# fpga.net
KiCad netlist of a schematic drawn in Altium Designer
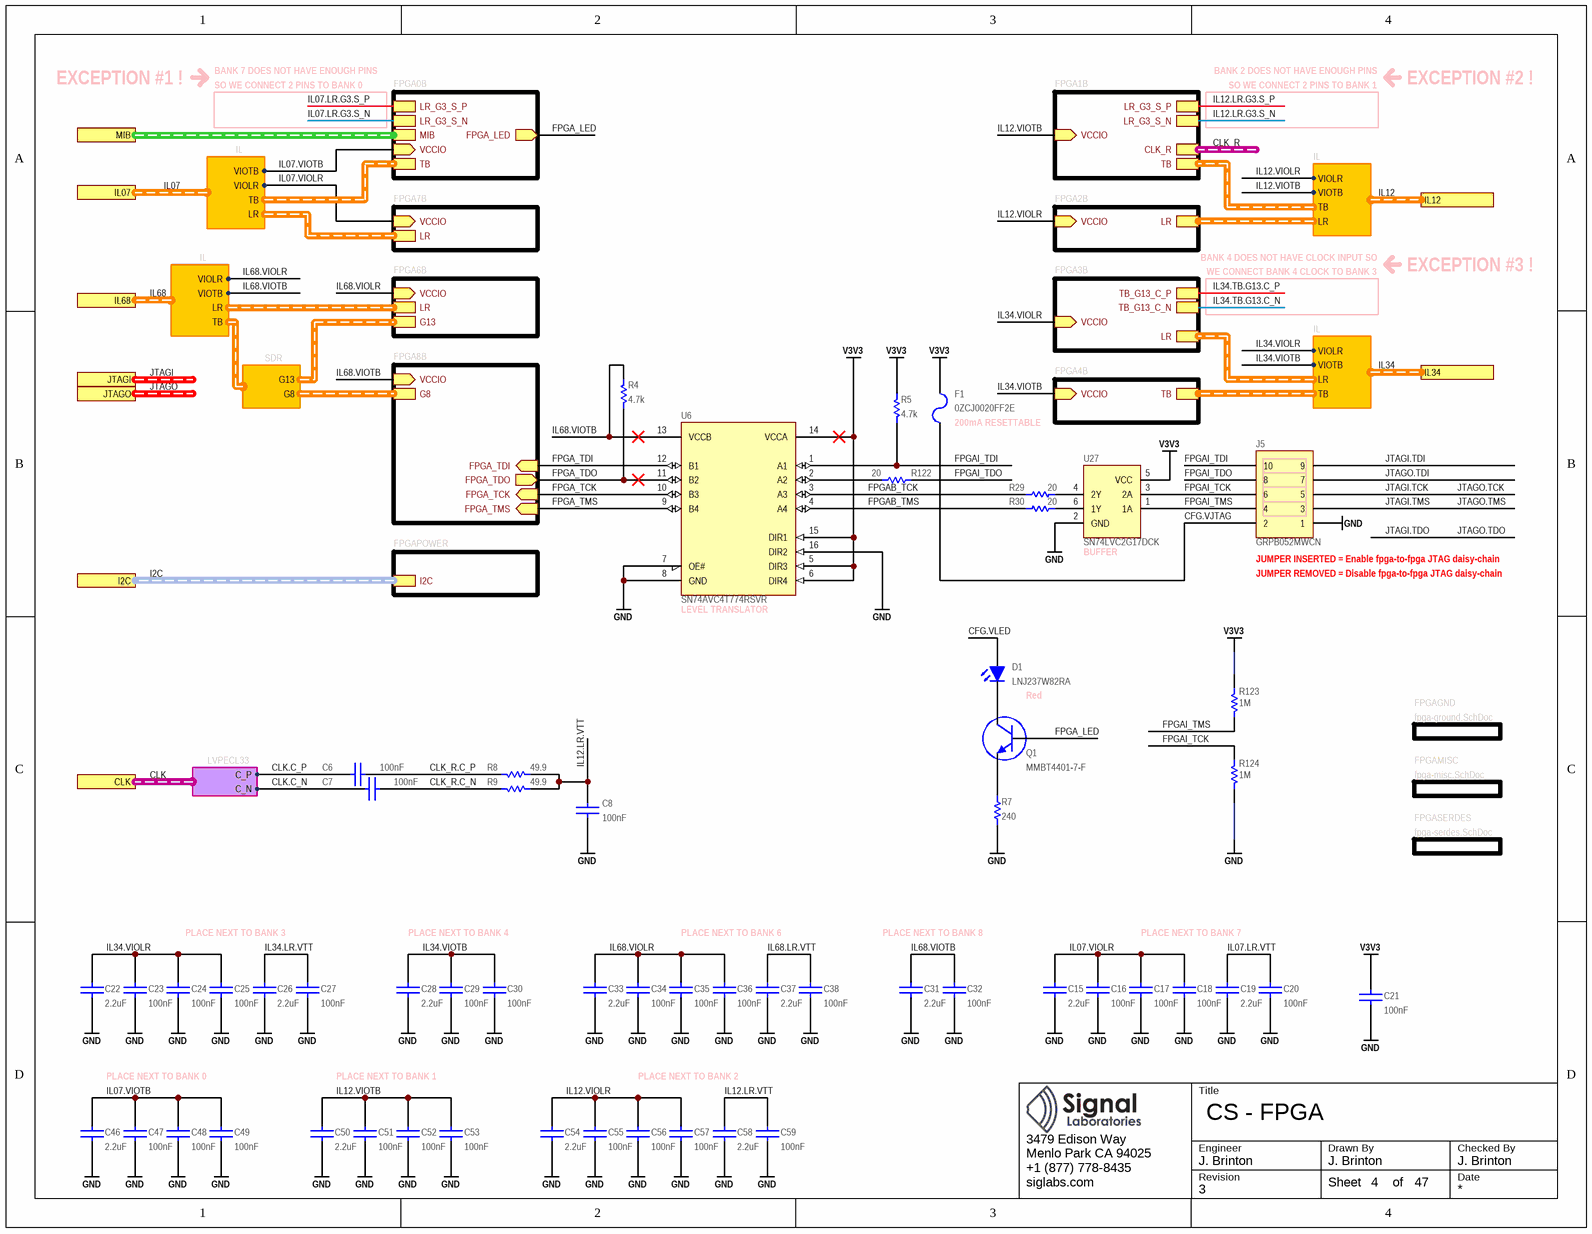
[diagram p0: fpga.SchDoc]

(export (version "E")
  (design (tool "Eeschema 10.0.6"))
  (components
    (comp (ref "C6")
      (value "100nF")
      (footprint "CAPC100X50X55L25N")
      (description "Ceramic Capacitor 100nF ±10% 50V X7R 0402")
      (fields (field (name "MANUFACTURER") "Murata") (field (name "TOLERANCE") "±10%"))
      (libsource (lib "generic") (part "CAP"))
    )
    (comp (ref "C7")
      (value "100nF")
      (footprint "CAPC100X50X55L25N")
      (description "Ceramic Capacitor 100nF ±10% 50V X7R 0402")
      (fields (field (name "MANUFACTURER") "Murata") (field (name "TOLERANCE") "±10%"))
      (libsource (lib "generic") (part "CAP"))
    )
    (comp (ref "C8")
      (value "100nF")
      (footprint "CAPC100X50X55L25N")
      (description "Ceramic Capacitor 100nF ±10% 50V X7R 0402")
      (fields (field (name "MANUFACTURER") "Murata") (field (name "TOLERANCE") "±10%"))
      (libsource (lib "generic") (part "CAP"))
    )
    (comp (ref "C15")
      (value "2.2uF")
      (footprint "CAPC160X80X90L20N")
      (description "Ceramic Capacitor 2.2uF ±20% 10V X7R 0603")
      (fields (field (name "MANUFACTURER") "TDK") (field (name "TOLERANCE") "±20%"))
      (libsource (lib "generic") (part "CAP"))
    )
    (comp (ref "C16")
      (value "100nF")
      (footprint "CAPC100X50X55L25N")
      (description "Ceramic Capacitor 100nF ±10% 50V X7R 0402")
      (fields (field (name "MANUFACTURER") "Murata") (field (name "TOLERANCE") "±10%"))
      (libsource (lib "generic") (part "CAP"))
    )
    (comp (ref "C17")
      (value "100nF")
      (footprint "CAPC100X50X55L25N")
      (description "Ceramic Capacitor 100nF ±10% 50V X7R 0402")
      (fields (field (name "MANUFACTURER") "Murata") (field (name "TOLERANCE") "±10%"))
      (libsource (lib "generic") (part "CAP"))
    )
    (comp (ref "C18")
      (value "100nF")
      (footprint "CAPC100X50X55L25N")
      (description "Ceramic Capacitor 100nF ±10% 50V X7R 0402")
      (fields (field (name "MANUFACTURER") "Murata") (field (name "TOLERANCE") "±10%"))
      (libsource (lib "generic") (part "CAP"))
    )
    (comp (ref "C19")
      (value "2.2uF")
      (footprint "CAPC160X80X90L20N")
      (description "Ceramic Capacitor 2.2uF ±20% 10V X7R 0603")
      (fields (field (name "MANUFACTURER") "TDK") (field (name "TOLERANCE") "±20%"))
      (libsource (lib "generic") (part "CAP"))
    )
    (comp (ref "C20")
      (value "100nF")
      (footprint "CAPC100X50X55L25N")
      (description "Ceramic Capacitor 100nF ±10% 50V X7R 0402")
      (fields (field (name "MANUFACTURER") "Murata") (field (name "TOLERANCE") "±10%"))
      (libsource (lib "generic") (part "CAP"))
    )
    (comp (ref "C21")
      (value "100nF")
      (footprint "CAPC100X50X55L25N")
      (description "Ceramic Capacitor 100nF ±10% 50V X7R 0402")
      (fields (field (name "MANUFACTURER") "Murata") (field (name "TOLERANCE") "±10%"))
      (libsource (lib "generic") (part "CAP"))
    )
    (comp (ref "C22")
      (value "2.2uF")
      (footprint "CAPC160X80X90L20N")
      (description "Ceramic Capacitor 2.2uF ±20% 10V X7R 0603")
      (fields (field (name "MANUFACTURER") "TDK") (field (name "TOLERANCE") "±20%"))
      (libsource (lib "generic") (part "CAP"))
    )
    (comp (ref "C23")
      (value "100nF")
      (footprint "CAPC100X50X55L25N")
      (description "Ceramic Capacitor 100nF ±10% 50V X7R 0402")
      (fields (field (name "MANUFACTURER") "Murata") (field (name "TOLERANCE") "±10%"))
      (libsource (lib "generic") (part "CAP"))
    )
    (comp (ref "C24")
      (value "100nF")
      (footprint "CAPC100X50X55L25N")
      (description "Ceramic Capacitor 100nF ±10% 50V X7R 0402")
      (fields (field (name "MANUFACTURER") "Murata") (field (name "TOLERANCE") "±10%"))
      (libsource (lib "generic") (part "CAP"))
    )
    (comp (ref "C25")
      (value "100nF")
      (footprint "CAPC100X50X55L25N")
      (description "Ceramic Capacitor 100nF ±10% 50V X7R 0402")
      (fields (field (name "MANUFACTURER") "Murata") (field (name "TOLERANCE") "±10%"))
      (libsource (lib "generic") (part "CAP"))
    )
    (comp (ref "C26")
      (value "2.2uF")
      (footprint "CAPC160X80X90L20N")
      (description "Ceramic Capacitor 2.2uF ±20% 10V X7R 0603")
      (fields (field (name "MANUFACTURER") "TDK") (field (name "TOLERANCE") "±20%"))
      (libsource (lib "generic") (part "CAP"))
    )
    (comp (ref "C27")
      (value "100nF")
      (footprint "CAPC100X50X55L25N")
      (description "Ceramic Capacitor 100nF ±10% 50V X7R 0402")
      (fields (field (name "MANUFACTURER") "Murata") (field (name "TOLERANCE") "±10%"))
      (libsource (lib "generic") (part "CAP"))
    )
    (comp (ref "C28")
      (value "2.2uF")
      (footprint "CAPC160X80X90L20N")
      (description "Ceramic Capacitor 2.2uF ±20% 10V X7R 0603")
      (fields (field (name "MANUFACTURER") "TDK") (field (name "TOLERANCE") "±20%"))
      (libsource (lib "generic") (part "CAP"))
    )
    (comp (ref "C29")
      (value "100nF")
      (footprint "CAPC100X50X55L25N")
      (description "Ceramic Capacitor 100nF ±10% 50V X7R 0402")
      (fields (field (name "MANUFACTURER") "Murata") (field (name "TOLERANCE") "±10%"))
      (libsource (lib "generic") (part "CAP"))
    )
    (comp (ref "C30")
      (value "100nF")
      (footprint "CAPC100X50X55L25N")
      (description "Ceramic Capacitor 100nF ±10% 50V X7R 0402")
      (fields (field (name "MANUFACTURER") "Murata") (field (name "TOLERANCE") "±10%"))
      (libsource (lib "generic") (part "CAP"))
    )
    (comp (ref "C31")
      (value "2.2uF")
      (footprint "CAPC160X80X90L20N")
      (description "Ceramic Capacitor 2.2uF ±20% 10V X7R 0603")
      (fields (field (name "MANUFACTURER") "TDK") (field (name "TOLERANCE") "±20%"))
      (libsource (lib "generic") (part "CAP"))
    )
    (comp (ref "C32")
      (value "100nF")
      (footprint "CAPC100X50X55L25N")
      (description "Ceramic Capacitor 100nF ±10% 50V X7R 0402")
      (fields (field (name "MANUFACTURER") "Murata") (field (name "TOLERANCE") "±10%"))
      (libsource (lib "generic") (part "CAP"))
    )
    (comp (ref "C33")
      (value "2.2uF")
      (footprint "CAPC160X80X90L20N")
      (description "Ceramic Capacitor 2.2uF ±20% 10V X7R 0603")
      (fields (field (name "MANUFACTURER") "TDK") (field (name "TOLERANCE") "±20%"))
      (libsource (lib "generic") (part "CAP"))
    )
    (comp (ref "C34")
      (value "100nF")
      (footprint "CAPC100X50X55L25N")
      (description "Ceramic Capacitor 100nF ±10% 50V X7R 0402")
      (fields (field (name "MANUFACTURER") "Murata") (field (name "TOLERANCE") "±10%"))
      (libsource (lib "generic") (part "CAP"))
    )
    (comp (ref "C35")
      (value "100nF")
      (footprint "CAPC100X50X55L25N")
      (description "Ceramic Capacitor 100nF ±10% 50V X7R 0402")
      (fields (field (name "MANUFACTURER") "Murata") (field (name "TOLERANCE") "±10%"))
      (libsource (lib "generic") (part "CAP"))
    )
    (comp (ref "C36")
      (value "100nF")
      (footprint "CAPC100X50X55L25N")
      (description "Ceramic Capacitor 100nF ±10% 50V X7R 0402")
      (fields (field (name "MANUFACTURER") "Murata") (field (name "TOLERANCE") "±10%"))
      (libsource (lib "generic") (part "CAP"))
    )
    (comp (ref "C37")
      (value "2.2uF")
      (footprint "CAPC160X80X90L20N")
      (description "Ceramic Capacitor 2.2uF ±20% 10V X7R 0603")
      (fields (field (name "MANUFACTURER") "TDK") (field (name "TOLERANCE") "±20%"))
      (libsource (lib "generic") (part "CAP"))
    )
    (comp (ref "C38")
      (value "100nF")
      (footprint "CAPC100X50X55L25N")
      (description "Ceramic Capacitor 100nF ±10% 50V X7R 0402")
      (fields (field (name "MANUFACTURER") "Murata") (field (name "TOLERANCE") "±10%"))
      (libsource (lib "generic") (part "CAP"))
    )
    (comp (ref "C46")
      (value "2.2uF")
      (footprint "CAPC160X80X90L20N")
      (description "Ceramic Capacitor 2.2uF ±20% 10V X7R 0603")
      (fields (field (name "MANUFACTURER") "TDK") (field (name "TOLERANCE") "±20%"))
      (libsource (lib "generic") (part "CAP"))
    )
    (comp (ref "C47")
      (value "100nF")
      (footprint "CAPC100X50X55L25N")
      (description "Ceramic Capacitor 100nF ±10% 50V X7R 0402")
      (fields (field (name "MANUFACTURER") "Murata") (field (name "TOLERANCE") "±10%"))
      (libsource (lib "generic") (part "CAP"))
    )
    (comp (ref "C48")
      (value "100nF")
      (footprint "CAPC100X50X55L25N")
      (description "Ceramic Capacitor 100nF ±10% 50V X7R 0402")
      (fields (field (name "MANUFACTURER") "Murata") (field (name "TOLERANCE") "±10%"))
      (libsource (lib "generic") (part "CAP"))
    )
    (comp (ref "C49")
      (value "100nF")
      (footprint "CAPC100X50X55L25N")
      (description "Ceramic Capacitor 100nF ±10% 50V X7R 0402")
      (fields (field (name "MANUFACTURER") "Murata") (field (name "TOLERANCE") "±10%"))
      (libsource (lib "generic") (part "CAP"))
    )
    (comp (ref "C50")
      (value "2.2uF")
      (footprint "CAPC160X80X90L20N")
      (description "Ceramic Capacitor 2.2uF ±20% 10V X7R 0603")
      (fields (field (name "MANUFACTURER") "TDK") (field (name "TOLERANCE") "±20%"))
      (libsource (lib "generic") (part "CAP"))
    )
    (comp (ref "C51")
      (value "100nF")
      (footprint "CAPC100X50X55L25N")
      (description "Ceramic Capacitor 100nF ±10% 50V X7R 0402")
      (fields (field (name "MANUFACTURER") "Murata") (field (name "TOLERANCE") "±10%"))
      (libsource (lib "generic") (part "CAP"))
    )
    (comp (ref "C52")
      (value "100nF")
      (footprint "CAPC100X50X55L25N")
      (description "Ceramic Capacitor 100nF ±10% 50V X7R 0402")
      (fields (field (name "MANUFACTURER") "Murata") (field (name "TOLERANCE") "±10%"))
      (libsource (lib "generic") (part "CAP"))
    )
    (comp (ref "C53")
      (value "100nF")
      (footprint "CAPC100X50X55L25N")
      (description "Ceramic Capacitor 100nF ±10% 50V X7R 0402")
      (fields (field (name "MANUFACTURER") "Murata") (field (name "TOLERANCE") "±10%"))
      (libsource (lib "generic") (part "CAP"))
    )
    (comp (ref "C54")
      (value "2.2uF")
      (footprint "CAPC160X80X90L20N")
      (description "Ceramic Capacitor 2.2uF ±20% 10V X7R 0603")
      (fields (field (name "MANUFACTURER") "TDK") (field (name "TOLERANCE") "±20%"))
      (libsource (lib "generic") (part "CAP"))
    )
    (comp (ref "C55")
      (value "100nF")
      (footprint "CAPC100X50X55L25N")
      (description "Ceramic Capacitor 100nF ±10% 50V X7R 0402")
      (fields (field (name "MANUFACTURER") "Murata") (field (name "TOLERANCE") "±10%"))
      (libsource (lib "generic") (part "CAP"))
    )
    (comp (ref "C56")
      (value "100nF")
      (footprint "CAPC100X50X55L25N")
      (description "Ceramic Capacitor 100nF ±10% 50V X7R 0402")
      (fields (field (name "MANUFACTURER") "Murata") (field (name "TOLERANCE") "±10%"))
      (libsource (lib "generic") (part "CAP"))
    )
    (comp (ref "C57")
      (value "100nF")
      (footprint "CAPC100X50X55L25N")
      (description "Ceramic Capacitor 100nF ±10% 50V X7R 0402")
      (fields (field (name "MANUFACTURER") "Murata") (field (name "TOLERANCE") "±10%"))
      (libsource (lib "generic") (part "CAP"))
    )
    (comp (ref "C58")
      (value "2.2uF")
      (footprint "CAPC160X80X90L20N")
      (description "Ceramic Capacitor 2.2uF ±20% 10V X7R 0603")
      (fields (field (name "MANUFACTURER") "TDK") (field (name "TOLERANCE") "±20%"))
      (libsource (lib "generic") (part "CAP"))
    )
    (comp (ref "C59")
      (value "100nF")
      (footprint "CAPC100X50X55L25N")
      (description "Ceramic Capacitor 100nF ±10% 50V X7R 0402")
      (fields (field (name "MANUFACTURER") "Murata") (field (name "TOLERANCE") "±10%"))
      (libsource (lib "generic") (part "CAP"))
    )
    (comp (ref "D1")
      (value "LNJ237W82RA")
      (footprint "0603_LED")
      (description "LED, SMT 0603, Color Red, 5mA, 1.85V")
      (fields (field (name "MANUFACTURER") "Panasonic"))
      (libsource (lib "generic") (part "LED0603RD"))
    )
    (comp (ref "F1")
      (value "0ZCJ0020FF2E")
      (footprint "generic:1206")
      (description "PTC Resettable Fuse, 0.2A, 30V, SMD 1206")
      (fields (field (name "MANUFACTURER") "Bell Fuse"))
      (libsource (lib "bel-fuse") (part "0ZCJ0020FF2E"))
    )
    (comp (ref "J5")
      (value "GRPB052MWCN")
      (footprint "sullins:GRPB052MWCN")
      (description "Male Header, 0.050\" Pitch, 2x5 Position, Right Angle")
      (fields (field (name "MANUFACTURER") "Sullins"))
      (libsource (lib "sullins") (part "GRPB052VWVN"))
    )
    (comp (ref "Q1")
      (value "MMBT4401-7-F")
      (footprint "generic:SOT23")
      (description "NPN Small Signal Transistor SMD SOT-23")
      (fields (field (name "MANUFACTURER P/N") "MMBT4401-7-F") (field (name "MANUFACTURER") "Diodes, Inc."))
      (libsource (lib "diodes_inc") (part "MMBT4401-7-F"))
    )
    (comp (ref "R4")
      (value "4.7k")
      (footprint "RESC1005X40N")
      (description "Thick Film Resistor 4.7k ±1% 0.1W 75V 0402")
      (fields (field (name "TOLERANCE") "±1%") (field (name "MANUFACTURER") "Panasonic"))
      (libsource (lib "generic") (part "RES"))
    )
    (comp (ref "R5")
      (value "4.7k")
      (footprint "RESC1005X40N")
      (description "Thick Film Resistor 4.7k ±1% 0.1W 75V 0402")
      (fields (field (name "TOLERANCE") "±1%") (field (name "MANUFACTURER") "Panasonic"))
      (libsource (lib "generic") (part "RES"))
    )
    (comp (ref "R7")
      (value "240")
      (footprint "RESC1005X40N")
      (description "Thick Film Resistor 240 ±1% 0.1W 75V 0402")
      (fields (field (name "TOLERANCE") "±1%") (field (name "MANUFACTURER") "Panasonic"))
      (libsource (lib "generic") (part "RES"))
    )
    (comp (ref "R8")
      (value "49.9")
      (footprint "RESC1005X40N")
      (description "Thick Film Resistor 49.9 ±1% 0.1W 50V 0402")
      (fields (field (name "TOLERANCE") "±1%") (field (name "MANUFACTURER") "Panasonic"))
      (libsource (lib "generic") (part "RES"))
    )
    (comp (ref "R9")
      (value "49.9")
      (footprint "RESC1005X40N")
      (description "Thick Film Resistor 49.9 ±1% 0.1W 50V 0402")
      (fields (field (name "TOLERANCE") "±1%") (field (name "MANUFACTURER") "Panasonic"))
      (libsource (lib "generic") (part "RES"))
    )
    (comp (ref "R29")
      (value "20")
      (footprint "RESC1005X40N")
      (description "Thick Film Resistor 20 ±1% 0.1W 75V 0402")
      (fields (field (name "TOLERANCE") "±1%") (field (name "MANUFACTURER") "Panasonic"))
      (libsource (lib "generic") (part "RES"))
    )
    (comp (ref "R30")
      (value "20")
      (footprint "RESC1005X40N")
      (description "Thick Film Resistor 20 ±1% 0.1W 75V 0402")
      (fields (field (name "TOLERANCE") "±1%") (field (name "MANUFACTURER") "Panasonic"))
      (libsource (lib "generic") (part "RES"))
    )
    (comp (ref "R122")
      (value "20")
      (footprint "RESC1005X40N")
      (description "Thick Film Resistor 20 ±1% 0.1W 75V 0402")
      (fields (field (name "TOLERANCE") "±1%") (field (name "MANUFACTURER") "Panasonic"))
      (libsource (lib "generic") (part "RES"))
    )
    (comp (ref "R123")
      (value "1M")
      (footprint "RESC1005X40N")
      (description "Thick Film Resistor 1M ±1% 0.1W 75V 0402")
      (fields (field (name "TOLERANCE") "±1%") (field (name "MANUFACTURER") "Panasonic"))
      (libsource (lib "generic") (part "RES"))
    )
    (comp (ref "R124")
      (value "1M")
      (footprint "RESC1005X40N")
      (description "Thick Film Resistor 1M ±1% 0.1W 75V 0402")
      (fields (field (name "TOLERANCE") "±1%") (field (name "MANUFACTURER") "Panasonic"))
      (libsource (lib "generic") (part "RES"))
    )
    (comp (ref "U6")
      (value "SN74AVC4T774RSVR")
      (footprint "RSV")
      (description "4-Bit Dual-Supply Bus Transceiver")
      (fields (field (name "MANUFACTURER") "Texas Instruments"))
      (libsource (lib "ti") (part "SN74AVC4T774RSVR"))
    )
    (comp (ref "U27")
      (value "SN74LVC2G17DCK")
      (footprint "texas_instruments:DCK-6")
      (description "Dual Schmitt-Trigger Buffer")
      (fields (field (name "MANUFACTURER") "Texas Instruments"))
      (libsource (lib "ti") (part "SN74LVC2G17DCK"))
    )
  )
  (nets
    (net (code "13") (name "/CFG.VJTAG") (class "Default")
      (node (ref "F1") (pin "2") (pinfunction "2_2") (pintype "passive"))
      (node (ref "J5") (pin "2") (pinfunction "2_2") (pintype "passive"))
    )
    (net (code "14") (name "/CFG.VLED") (class "Default")
      (node (ref "D1") (pin "1") (pinfunction "A_1") (pintype "passive"))
    )
    (net (code "15") (name "/CLK.C_N") (class "Default")
      (node (ref "C7") (pin "2") (pinfunction "2_2") (pintype "passive"))
    )
    (net (code "16") (name "/CLK.C_P") (class "Default")
      (node (ref "C6") (pin "2") (pinfunction "2_2") (pintype "passive"))
    )
    (net (code "17") (name "/CLK_R.C_N") (class "Default")
      (node (ref "C7") (pin "1") (pinfunction "1_1") (pintype "passive"))
      (node (ref "R9") (pin "2") (pinfunction "2_2") (pintype "passive"))
    )
    (net (code "18") (name "/CLK_R.C_P") (class "Default")
      (node (ref "C6") (pin "1") (pinfunction "1_1") (pintype "passive"))
      (node (ref "R8") (pin "2") (pinfunction "2_2") (pintype "passive"))
    )
    (net (code "20") (name "/FPGAB_TCK") (class "Default")
      (node (ref "R29") (pin "1") (pinfunction "1_1") (pintype "passive"))
      (node (ref "U6") (pin "3") (pinfunction "A3_3") (pintype "bidirectional"))
    )
    (net (code "21") (name "/FPGAB_TMS") (class "Default")
      (node (ref "R30") (pin "1") (pinfunction "1_1") (pintype "passive"))
      (node (ref "U6") (pin "4") (pinfunction "A4_4") (pintype "bidirectional"))
    )
    (net (code "22") (name "/FPGAI_TCK") (class "Default")
      (node (ref "J5") (pin "6") (pinfunction "6_6") (pintype "passive"))
      (node (ref "R124") (pin "1") (pinfunction "1_1") (pintype "passive"))
      (node (ref "U27") (pin "3") (pinfunction "2A_3") (pintype "passive"))
    )
    (net (code "23") (name "/FPGAI_TDI") (class "Default")
      (node (ref "J5") (pin "10") (pinfunction "10_10") (pintype "passive"))
      (node (ref "R5") (pin "1") (pinfunction "1_1") (pintype "passive"))
      (node (ref "U6") (pin "1") (pinfunction "A1_1") (pintype "bidirectional"))
    )
    (net (code "24") (name "/FPGAI_TDO") (class "Default")
      (node (ref "J5") (pin "8") (pinfunction "8_8") (pintype "passive"))
      (node (ref "R122") (pin "2") (pinfunction "2_2") (pintype "passive"))
    )
    (net (code "25") (name "/FPGAI_TMS") (class "Default")
      (node (ref "J5") (pin "4") (pinfunction "4_4") (pintype "passive"))
      (node (ref "R123") (pin "2") (pinfunction "2_2") (pintype "passive"))
      (node (ref "U27") (pin "1") (pinfunction "1A_1") (pintype "passive"))
    )
    (net (code "26") (name "/FPGA_LED") (class "Default")
      (node (ref "Q1") (pin "1") (pinfunction "B_1") (pintype "passive"))
    )
    (net (code "27") (name "/FPGA_TCK") (class "Default")
      (node (ref "U6") (pin "10") (pinfunction "B3_10") (pintype "bidirectional"))
    )
    (net (code "28") (name "/FPGA_TDI") (class "Default")
      (node (ref "U6") (pin "12") (pinfunction "B1_12") (pintype "bidirectional"))
    )
    (net (code "29") (name "/FPGA_TDO") (class "Default")
      (node (ref "R4") (pin "1") (pinfunction "1_1") (pintype "passive"))
      (node (ref "U6") (pin "11") (pinfunction "B2_11") (pintype "bidirectional"))
    )
    (net (code "30") (name "/FPGA_TMS") (class "Default")
      (node (ref "U6") (pin "9") (pinfunction "B4_9") (pintype "bidirectional"))
    )
    (net (code "33") (name "/IL07.LR.VTT") (class "Default")
      (node (ref "C19") (pin "2") (pinfunction "2_2") (pintype "passive"))
      (node (ref "C20") (pin "2") (pinfunction "2_2") (pintype "passive"))
    )
    (net (code "34") (name "/IL07.VIOLR") (class "Default")
      (node (ref "C15") (pin "2") (pinfunction "2_2") (pintype "passive"))
      (node (ref "C16") (pin "2") (pinfunction "2_2") (pintype "passive"))
      (node (ref "C17") (pin "2") (pinfunction "2_2") (pintype "passive"))
      (node (ref "C18") (pin "2") (pinfunction "2_2") (pintype "passive"))
    )
    (net (code "35") (name "/IL07.VIOTB") (class "Default")
      (node (ref "C46") (pin "2") (pinfunction "2_2") (pintype "passive"))
      (node (ref "C47") (pin "2") (pinfunction "2_2") (pintype "passive"))
      (node (ref "C48") (pin "2") (pinfunction "2_2") (pintype "passive"))
      (node (ref "C49") (pin "2") (pinfunction "2_2") (pintype "passive"))
    )
    (net (code "38") (name "/IL12.LR.VTT") (class "Default")
      (node (ref "C58") (pin "2") (pinfunction "2_2") (pintype "passive"))
      (node (ref "C59") (pin "2") (pinfunction "2_2") (pintype "passive"))
      (node (ref "C8") (pin "2") (pinfunction "2_2") (pintype "passive"))
      (node (ref "R8") (pin "1") (pinfunction "1_1") (pintype "passive"))
      (node (ref "R9") (pin "1") (pinfunction "1_1") (pintype "passive"))
    )
    (net (code "39") (name "/IL12.VIOLR") (class "Default")
      (node (ref "C54") (pin "2") (pinfunction "2_2") (pintype "passive"))
      (node (ref "C55") (pin "2") (pinfunction "2_2") (pintype "passive"))
      (node (ref "C56") (pin "2") (pinfunction "2_2") (pintype "passive"))
      (node (ref "C57") (pin "2") (pinfunction "2_2") (pintype "passive"))
    )
    (net (code "40") (name "/IL12.VIOTB") (class "Default")
      (node (ref "C50") (pin "2") (pinfunction "2_2") (pintype "passive"))
      (node (ref "C51") (pin "2") (pinfunction "2_2") (pintype "passive"))
      (node (ref "C52") (pin "2") (pinfunction "2_2") (pintype "passive"))
      (node (ref "C53") (pin "2") (pinfunction "2_2") (pintype "passive"))
    )
    (net (code "41") (name "/IL34.LR.VTT") (class "Default")
      (node (ref "C26") (pin "2") (pinfunction "2_2") (pintype "passive"))
      (node (ref "C27") (pin "2") (pinfunction "2_2") (pintype "passive"))
    )
    (net (code "44") (name "/IL34.VIOLR") (class "Default")
      (node (ref "C22") (pin "2") (pinfunction "2_2") (pintype "passive"))
      (node (ref "C23") (pin "2") (pinfunction "2_2") (pintype "passive"))
      (node (ref "C24") (pin "2") (pinfunction "2_2") (pintype "passive"))
      (node (ref "C25") (pin "2") (pinfunction "2_2") (pintype "passive"))
    )
    (net (code "45") (name "/IL34.VIOTB") (class "Default")
      (node (ref "C28") (pin "2") (pinfunction "2_2") (pintype "passive"))
      (node (ref "C29") (pin "2") (pinfunction "2_2") (pintype "passive"))
      (node (ref "C30") (pin "2") (pinfunction "2_2") (pintype "passive"))
    )
    (net (code "46") (name "/IL68.LR.VTT") (class "Default")
      (node (ref "C37") (pin "2") (pinfunction "2_2") (pintype "passive"))
      (node (ref "C38") (pin "2") (pinfunction "2_2") (pintype "passive"))
    )
    (net (code "47") (name "/IL68.VIOLR") (class "Default")
      (node (ref "C33") (pin "2") (pinfunction "2_2") (pintype "passive"))
      (node (ref "C34") (pin "2") (pinfunction "2_2") (pintype "passive"))
      (node (ref "C35") (pin "2") (pinfunction "2_2") (pintype "passive"))
      (node (ref "C36") (pin "2") (pinfunction "2_2") (pintype "passive"))
    )
    (net (code "48") (name "/IL68.VIOTB") (class "Default")
      (node (ref "C31") (pin "2") (pinfunction "2_2") (pintype "passive"))
      (node (ref "C32") (pin "2") (pinfunction "2_2") (pintype "passive"))
      (node (ref "R4") (pin "2") (pinfunction "2_2") (pintype "passive"))
      (node (ref "U6") (pin "13") (pinfunction "VCCB_13") (pintype "power_in"))
    )
    (net (code "49") (name "/JTAGI.TCK") (class "Default")
      (node (ref "J5") (pin "5") (pinfunction "5_5") (pintype "passive"))
    )
    (net (code "50") (name "/JTAGI.TDI") (class "Default")
      (node (ref "J5") (pin "9") (pinfunction "9_9") (pintype "passive"))
    )
    (net (code "52") (name "/JTAGI.TMS") (class "Default")
      (node (ref "J5") (pin "3") (pinfunction "3_3") (pintype "passive"))
    )
    (net (code "53") (name "/JTAGO.TDI") (class "Default")
      (node (ref "J5") (pin "7") (pinfunction "7_7") (pintype "passive"))
    )
    (net (code "67") (name "GND") (class "Default")
      (node (ref "C15") (pin "1") (pinfunction "1_1") (pintype "passive"))
      (node (ref "C16") (pin "1") (pinfunction "1_1") (pintype "passive"))
      (node (ref "C17") (pin "1") (pinfunction "1_1") (pintype "passive"))
      (node (ref "C18") (pin "1") (pinfunction "1_1") (pintype "passive"))
      (node (ref "C19") (pin "1") (pinfunction "1_1") (pintype "passive"))
      (node (ref "C20") (pin "1") (pinfunction "1_1") (pintype "passive"))
      (node (ref "C21") (pin "1") (pinfunction "1_1") (pintype "passive"))
      (node (ref "C22") (pin "1") (pinfunction "1_1") (pintype "passive"))
      (node (ref "C23") (pin "1") (pinfunction "1_1") (pintype "passive"))
      (node (ref "C24") (pin "1") (pinfunction "1_1") (pintype "passive"))
      (node (ref "C25") (pin "1") (pinfunction "1_1") (pintype "passive"))
      (node (ref "C26") (pin "1") (pinfunction "1_1") (pintype "passive"))
      (node (ref "C27") (pin "1") (pinfunction "1_1") (pintype "passive"))
      (node (ref "C28") (pin "1") (pinfunction "1_1") (pintype "passive"))
      (node (ref "C29") (pin "1") (pinfunction "1_1") (pintype "passive"))
      (node (ref "C30") (pin "1") (pinfunction "1_1") (pintype "passive"))
      (node (ref "C31") (pin "1") (pinfunction "1_1") (pintype "passive"))
      (node (ref "C32") (pin "1") (pinfunction "1_1") (pintype "passive"))
      (node (ref "C33") (pin "1") (pinfunction "1_1") (pintype "passive"))
      (node (ref "C34") (pin "1") (pinfunction "1_1") (pintype "passive"))
      (node (ref "C35") (pin "1") (pinfunction "1_1") (pintype "passive"))
      (node (ref "C36") (pin "1") (pinfunction "1_1") (pintype "passive"))
      (node (ref "C37") (pin "1") (pinfunction "1_1") (pintype "passive"))
      (node (ref "C38") (pin "1") (pinfunction "1_1") (pintype "passive"))
      (node (ref "C46") (pin "1") (pinfunction "1_1") (pintype "passive"))
      (node (ref "C47") (pin "1") (pinfunction "1_1") (pintype "passive"))
      (node (ref "C48") (pin "1") (pinfunction "1_1") (pintype "passive"))
      (node (ref "C49") (pin "1") (pinfunction "1_1") (pintype "passive"))
      (node (ref "C50") (pin "1") (pinfunction "1_1") (pintype "passive"))
      (node (ref "C51") (pin "1") (pinfunction "1_1") (pintype "passive"))
      (node (ref "C52") (pin "1") (pinfunction "1_1") (pintype "passive"))
      (node (ref "C53") (pin "1") (pinfunction "1_1") (pintype "passive"))
      (node (ref "C54") (pin "1") (pinfunction "1_1") (pintype "passive"))
      (node (ref "C55") (pin "1") (pinfunction "1_1") (pintype "passive"))
      (node (ref "C56") (pin "1") (pinfunction "1_1") (pintype "passive"))
      (node (ref "C57") (pin "1") (pinfunction "1_1") (pintype "passive"))
      (node (ref "C58") (pin "1") (pinfunction "1_1") (pintype "passive"))
      (node (ref "C59") (pin "1") (pinfunction "1_1") (pintype "passive"))
      (node (ref "C8") (pin "1") (pinfunction "1_1") (pintype "passive"))
      (node (ref "J5") (pin "1") (pinfunction "1_1") (pintype "passive"))
      (node (ref "R124") (pin "2") (pinfunction "2_2") (pintype "passive"))
      (node (ref "R7") (pin "2") (pinfunction "2_2") (pintype "passive"))
      (node (ref "U27") (pin "2") (pinfunction "GND_2") (pintype "passive"))
      (node (ref "U6") (pin "16") (pinfunction "DIR2_16") (pintype "input"))
      (node (ref "U6") (pin "7") (pinfunction "OE#_7") (pintype "passive"))
      (node (ref "U6") (pin "8") (pinfunction "GND_8") (pintype "power_in"))
    )
    (net (code "68") (name "Net-(D1-K)") (class "Default")
      (node (ref "D1") (pin "2") (pinfunction "K_2") (pintype "passive"))
      (node (ref "Q1") (pin "3") (pinfunction "C_3") (pintype "passive"))
    )
    (net (code "69") (name "Net-(Q1-E)") (class "Default")
      (node (ref "Q1") (pin "2") (pinfunction "E_2") (pintype "passive"))
      (node (ref "R7") (pin "1") (pinfunction "1_1") (pintype "passive"))
    )
    (net (code "70") (name "Net-(U6-A2)") (class "Default")
      (node (ref "R122") (pin "1") (pinfunction "1_1") (pintype "passive"))
      (node (ref "U6") (pin "2") (pinfunction "A2_2") (pintype "bidirectional"))
    )
    (net (code "71") (name "Net-(U27-1Y)") (class "Default")
      (node (ref "R30") (pin "2") (pinfunction "2_2") (pintype "passive"))
      (node (ref "U27") (pin "6") (pinfunction "1Y_6") (pintype "passive"))
    )
    (net (code "72") (name "Net-(U27-2Y)") (class "Default")
      (node (ref "R29") (pin "2") (pinfunction "2_2") (pintype "passive"))
      (node (ref "U27") (pin "4") (pinfunction "2Y_4") (pintype "passive"))
    )
    (net (code "73") (name "V3V3") (class "Default")
      (node (ref "C21") (pin "2") (pinfunction "2_2") (pintype "passive"))
      (node (ref "F1") (pin "1") (pinfunction "1_1") (pintype "passive"))
      (node (ref "R123") (pin "1") (pinfunction "1_1") (pintype "passive"))
      (node (ref "R5") (pin "2") (pinfunction "2_2") (pintype "passive"))
      (node (ref "U27") (pin "5") (pinfunction "VCC_5") (pintype "passive"))
      (node (ref "U6") (pin "14") (pinfunction "VCCA_14") (pintype "power_in"))
      (node (ref "U6") (pin "15") (pinfunction "DIR1_15") (pintype "input"))
      (node (ref "U6") (pin "5") (pinfunction "DIR3_5") (pintype "input"))
      (node (ref "U6") (pin "6") (pinfunction "DIR4_6") (pintype "input"))
    )
  )
)
